# misc.net
KiCad netlist of a schematic drawn in EAGLE
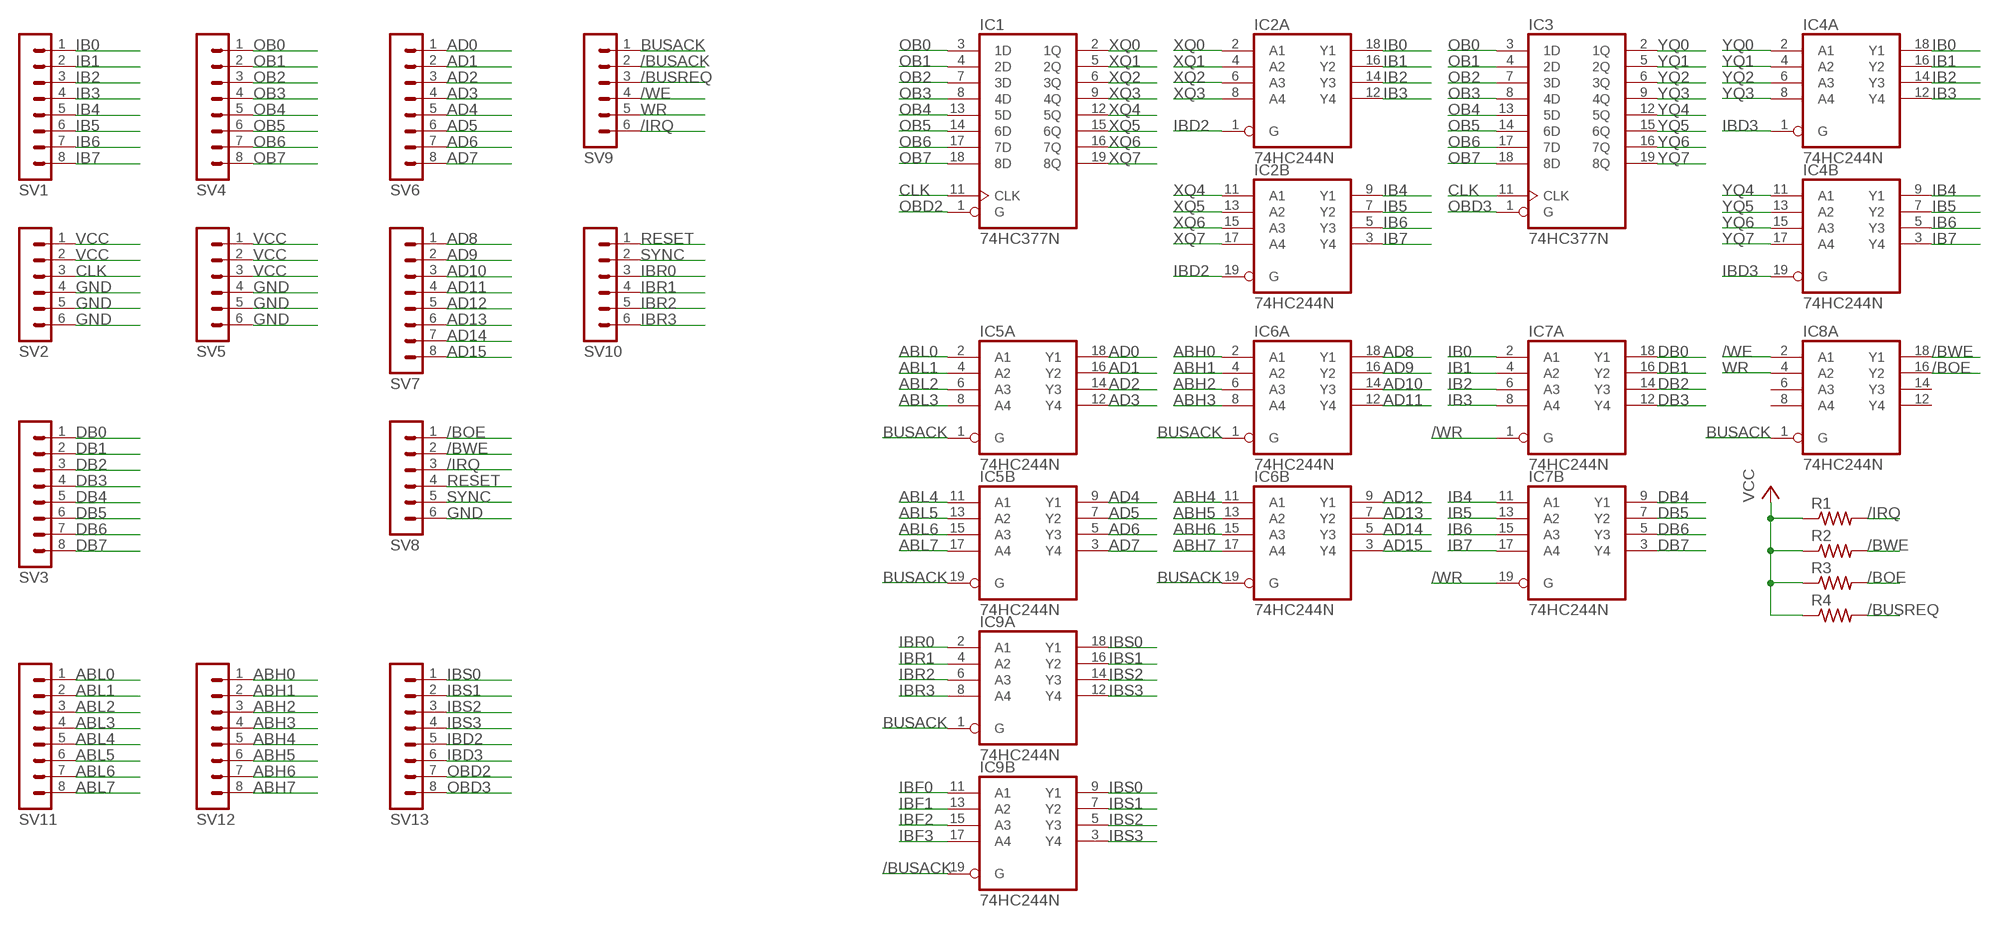
[diagram p0: schematic, sheet 1]

(export (version "E")
  (design (tool "Eeschema 10.0.6"))
  (components
    (comp (ref "IC1")
      (value "74HC377N")
      (footprint "eagle-import:DIL20")
      (libsource (lib "eagle-import") (part "74377NHC"))
    )
    (comp (ref "IC2")
      (value "74HC244N")
      (footprint "eagle-import:DIL20")
      (libsource (lib "eagle-import") (part "74244NHC"))
    )
    (comp (ref "IC3")
      (value "74HC377N")
      (footprint "eagle-import:DIL20")
      (libsource (lib "eagle-import") (part "74377NHC"))
    )
    (comp (ref "IC4")
      (value "74HC244N")
      (footprint "eagle-import:DIL20")
      (libsource (lib "eagle-import") (part "74244NHC"))
    )
    (comp (ref "IC5")
      (value "74HC244N")
      (footprint "eagle-import:DIL20")
      (libsource (lib "eagle-import") (part "74244NHC"))
    )
    (comp (ref "IC6")
      (value "74HC244N")
      (footprint "eagle-import:DIL20")
      (libsource (lib "eagle-import") (part "74244NHC"))
    )
    (comp (ref "IC7")
      (value "74HC244N")
      (footprint "eagle-import:DIL20")
      (libsource (lib "eagle-import") (part "74244NHC"))
    )
    (comp (ref "IC8")
      (value "74HC244N")
      (footprint "eagle-import:DIL20")
      (libsource (lib "eagle-import") (part "74244NHC"))
    )
    (comp (ref "IC9")
      (value "74HC244N")
      (footprint "eagle-import:DIL20")
      (libsource (lib "eagle-import") (part "74244NHC"))
    )
    (comp (ref "R1")
      (value "R-US_0207/10")
      (footprint "eagle-import:0207_10")
      (libsource (lib "eagle-import") (part "R-US_0207/10"))
    )
    (comp (ref "R2")
      (value "R-US_0207/10")
      (footprint "eagle-import:0207_10")
      (libsource (lib "eagle-import") (part "R-US_0207/10"))
    )
    (comp (ref "R3")
      (value "R-US_0207/10")
      (footprint "eagle-import:0207_10")
      (libsource (lib "eagle-import") (part "R-US_0207/10"))
    )
    (comp (ref "R4")
      (value "R-US_0207/10")
      (footprint "eagle-import:0207_10")
      (libsource (lib "eagle-import") (part "R-US_0207/10"))
    )
    (comp (ref "SV1")
      (value "MA08-1")
      (footprint "eagle-import:MA08-1")
      (libsource (lib "eagle-import") (part "MA08-1"))
    )
    (comp (ref "SV2")
      (value "MA06-1")
      (footprint "eagle-import:MA06-1")
      (libsource (lib "eagle-import") (part "MA06-1"))
    )
    (comp (ref "SV3")
      (value "MA08-1")
      (footprint "eagle-import:MA08-1")
      (libsource (lib "eagle-import") (part "MA08-1"))
    )
    (comp (ref "SV4")
      (value "MA08-1")
      (footprint "eagle-import:MA08-1")
      (libsource (lib "eagle-import") (part "MA08-1"))
    )
    (comp (ref "SV5")
      (value "MA06-1")
      (footprint "eagle-import:MA06-1")
      (libsource (lib "eagle-import") (part "MA06-1"))
    )
    (comp (ref "SV6")
      (value "MA08-1")
      (footprint "eagle-import:MA08-1")
      (libsource (lib "eagle-import") (part "MA08-1"))
    )
    (comp (ref "SV7")
      (value "MA08-1")
      (footprint "eagle-import:MA08-1")
      (libsource (lib "eagle-import") (part "MA08-1"))
    )
    (comp (ref "SV8")
      (value "MA06-1")
      (footprint "eagle-import:MA06-1")
      (libsource (lib "eagle-import") (part "MA06-1"))
    )
    (comp (ref "SV9")
      (value "MA06-1")
      (footprint "eagle-import:MA06-1")
      (libsource (lib "eagle-import") (part "MA06-1"))
    )
    (comp (ref "SV10")
      (value "MA06-1")
      (footprint "eagle-import:MA06-1")
      (libsource (lib "eagle-import") (part "MA06-1"))
    )
    (comp (ref "SV11")
      (value "MA08-1")
      (footprint "eagle-import:MA08-1")
      (libsource (lib "eagle-import") (part "MA08-1"))
    )
    (comp (ref "SV12")
      (value "MA08-1")
      (footprint "eagle-import:MA08-1")
      (libsource (lib "eagle-import") (part "MA08-1"))
    )
    (comp (ref "SV13")
      (value "MA08-1")
      (footprint "eagle-import:MA08-1")
      (libsource (lib "eagle-import") (part "MA08-1"))
    )
  )
  (nets
    (net (code "1") (name "/ABH0") (class "Default")
      (node (ref "IC6") (pin "2") (pinfunction "A1_2") (pintype "input"))
      (node (ref "SV12") (pin "1") (pinfunction "1_1") (pintype "passive"))
    )
    (net (code "2") (name "/ABH1") (class "Default")
      (node (ref "IC6") (pin "4") (pinfunction "A2_4") (pintype "input"))
      (node (ref "SV12") (pin "2") (pinfunction "2_2") (pintype "passive"))
    )
    (net (code "3") (name "/ABH2") (class "Default")
      (node (ref "IC6") (pin "6") (pinfunction "A3_6") (pintype "input"))
      (node (ref "SV12") (pin "3") (pinfunction "3_3") (pintype "passive"))
    )
    (net (code "4") (name "/ABH3") (class "Default")
      (node (ref "IC6") (pin "8") (pinfunction "A4_8") (pintype "input"))
      (node (ref "SV12") (pin "4") (pinfunction "4_4") (pintype "passive"))
    )
    (net (code "5") (name "/ABH4") (class "Default")
      (node (ref "IC6") (pin "11") (pinfunction "A1_11") (pintype "input"))
      (node (ref "SV12") (pin "5") (pinfunction "5_5") (pintype "passive"))
    )
    (net (code "6") (name "/ABH5") (class "Default")
      (node (ref "IC6") (pin "13") (pinfunction "A2_13") (pintype "input"))
      (node (ref "SV12") (pin "6") (pinfunction "6_6") (pintype "passive"))
    )
    (net (code "7") (name "/ABH6") (class "Default")
      (node (ref "IC6") (pin "15") (pinfunction "A3_15") (pintype "input"))
      (node (ref "SV12") (pin "7") (pinfunction "7_7") (pintype "passive"))
    )
    (net (code "8") (name "/ABH7") (class "Default")
      (node (ref "IC6") (pin "17") (pinfunction "A4_17") (pintype "input"))
      (node (ref "SV12") (pin "8") (pinfunction "8_8") (pintype "passive"))
    )
    (net (code "9") (name "/ABL0") (class "Default")
      (node (ref "IC5") (pin "2") (pinfunction "A1_2") (pintype "input"))
      (node (ref "SV11") (pin "1") (pinfunction "1_1") (pintype "passive"))
    )
    (net (code "10") (name "/ABL1") (class "Default")
      (node (ref "IC5") (pin "4") (pinfunction "A2_4") (pintype "input"))
      (node (ref "SV11") (pin "2") (pinfunction "2_2") (pintype "passive"))
    )
    (net (code "11") (name "/ABL2") (class "Default")
      (node (ref "IC5") (pin "6") (pinfunction "A3_6") (pintype "input"))
      (node (ref "SV11") (pin "3") (pinfunction "3_3") (pintype "passive"))
    )
    (net (code "12") (name "/ABL3") (class "Default")
      (node (ref "IC5") (pin "8") (pinfunction "A4_8") (pintype "input"))
      (node (ref "SV11") (pin "4") (pinfunction "4_4") (pintype "passive"))
    )
    (net (code "13") (name "/ABL4") (class "Default")
      (node (ref "IC5") (pin "11") (pinfunction "A1_11") (pintype "input"))
      (node (ref "SV11") (pin "5") (pinfunction "5_5") (pintype "passive"))
    )
    (net (code "14") (name "/ABL5") (class "Default")
      (node (ref "IC5") (pin "13") (pinfunction "A2_13") (pintype "input"))
      (node (ref "SV11") (pin "6") (pinfunction "6_6") (pintype "passive"))
    )
    (net (code "15") (name "/ABL6") (class "Default")
      (node (ref "IC5") (pin "15") (pinfunction "A3_15") (pintype "input"))
      (node (ref "SV11") (pin "7") (pinfunction "7_7") (pintype "passive"))
    )
    (net (code "16") (name "/ABL7") (class "Default")
      (node (ref "IC5") (pin "17") (pinfunction "A4_17") (pintype "input"))
      (node (ref "SV11") (pin "8") (pinfunction "8_8") (pintype "passive"))
    )
    (net (code "17") (name "/AD0") (class "Default")
      (node (ref "IC5") (pin "18") (pinfunction "Y1_18") (pintype "tri_state"))
      (node (ref "SV6") (pin "1") (pinfunction "1_1") (pintype "passive"))
    )
    (net (code "18") (name "/AD1") (class "Default")
      (node (ref "IC5") (pin "16") (pinfunction "Y2_16") (pintype "tri_state"))
      (node (ref "SV6") (pin "2") (pinfunction "2_2") (pintype "passive"))
    )
    (net (code "19") (name "/AD2") (class "Default")
      (node (ref "IC5") (pin "14") (pinfunction "Y3_14") (pintype "tri_state"))
      (node (ref "SV6") (pin "3") (pinfunction "3_3") (pintype "passive"))
    )
    (net (code "20") (name "/AD3") (class "Default")
      (node (ref "IC5") (pin "12") (pinfunction "Y4_12") (pintype "tri_state"))
      (node (ref "SV6") (pin "4") (pinfunction "4_4") (pintype "passive"))
    )
    (net (code "21") (name "/AD4") (class "Default")
      (node (ref "IC5") (pin "9") (pinfunction "Y1_9") (pintype "tri_state"))
      (node (ref "SV6") (pin "5") (pinfunction "5_5") (pintype "passive"))
    )
    (net (code "22") (name "/AD5") (class "Default")
      (node (ref "IC5") (pin "7") (pinfunction "Y2_7") (pintype "tri_state"))
      (node (ref "SV6") (pin "6") (pinfunction "6_6") (pintype "passive"))
    )
    (net (code "23") (name "/AD6") (class "Default")
      (node (ref "IC5") (pin "5") (pinfunction "Y3_5") (pintype "tri_state"))
      (node (ref "SV6") (pin "7") (pinfunction "7_7") (pintype "passive"))
    )
    (net (code "24") (name "/AD7") (class "Default")
      (node (ref "IC5") (pin "3") (pinfunction "Y4_3") (pintype "tri_state"))
      (node (ref "SV6") (pin "8") (pinfunction "8_8") (pintype "passive"))
    )
    (net (code "25") (name "/AD8") (class "Default")
      (node (ref "IC6") (pin "18") (pinfunction "Y1_18") (pintype "tri_state"))
      (node (ref "SV7") (pin "1") (pinfunction "1_1") (pintype "passive"))
    )
    (net (code "26") (name "/AD9") (class "Default")
      (node (ref "IC6") (pin "16") (pinfunction "Y2_16") (pintype "tri_state"))
      (node (ref "SV7") (pin "2") (pinfunction "2_2") (pintype "passive"))
    )
    (net (code "27") (name "/AD10") (class "Default")
      (node (ref "IC6") (pin "14") (pinfunction "Y3_14") (pintype "tri_state"))
      (node (ref "SV7") (pin "3") (pinfunction "3_3") (pintype "passive"))
    )
    (net (code "28") (name "/AD11") (class "Default")
      (node (ref "IC6") (pin "12") (pinfunction "Y4_12") (pintype "tri_state"))
      (node (ref "SV7") (pin "4") (pinfunction "4_4") (pintype "passive"))
    )
    (net (code "29") (name "/AD12") (class "Default")
      (node (ref "IC6") (pin "9") (pinfunction "Y1_9") (pintype "tri_state"))
      (node (ref "SV7") (pin "5") (pinfunction "5_5") (pintype "passive"))
    )
    (net (code "30") (name "/AD13") (class "Default")
      (node (ref "IC6") (pin "7") (pinfunction "Y2_7") (pintype "tri_state"))
      (node (ref "SV7") (pin "6") (pinfunction "6_6") (pintype "passive"))
    )
    (net (code "31") (name "/AD14") (class "Default")
      (node (ref "IC6") (pin "5") (pinfunction "Y3_5") (pintype "tri_state"))
      (node (ref "SV7") (pin "7") (pinfunction "7_7") (pintype "passive"))
    )
    (net (code "32") (name "/AD15") (class "Default")
      (node (ref "IC6") (pin "3") (pinfunction "Y4_3") (pintype "tri_state"))
      (node (ref "SV7") (pin "8") (pinfunction "8_8") (pintype "passive"))
    )
    (net (code "33") (name "/BUSACK") (class "Default")
      (node (ref "IC5") (pin "1") (pinfunction "G_1") (pintype "input"))
      (node (ref "IC5") (pin "19") (pinfunction "G_19") (pintype "input"))
      (node (ref "IC6") (pin "1") (pinfunction "G_1") (pintype "input"))
      (node (ref "IC6") (pin "19") (pinfunction "G_19") (pintype "input"))
      (node (ref "IC8") (pin "1") (pinfunction "G_1") (pintype "input"))
      (node (ref "IC9") (pin "1") (pinfunction "G_1") (pintype "input"))
      (node (ref "SV9") (pin "1") (pinfunction "1_1") (pintype "passive"))
    )
    (net (code "34") (name "/CLK") (class "Default")
      (node (ref "IC1") (pin "11") (pinfunction "CLK_11") (pintype "input"))
      (node (ref "IC3") (pin "11") (pinfunction "CLK_11") (pintype "input"))
      (node (ref "SV2") (pin "3") (pinfunction "3_3") (pintype "passive"))
    )
    (net (code "35") (name "/DB0") (class "Default")
      (node (ref "IC7") (pin "18") (pinfunction "Y1_18") (pintype "tri_state"))
      (node (ref "SV3") (pin "1") (pinfunction "1_1") (pintype "passive"))
    )
    (net (code "36") (name "/DB1") (class "Default")
      (node (ref "IC7") (pin "16") (pinfunction "Y2_16") (pintype "tri_state"))
      (node (ref "SV3") (pin "2") (pinfunction "2_2") (pintype "passive"))
    )
    (net (code "37") (name "/DB2") (class "Default")
      (node (ref "IC7") (pin "14") (pinfunction "Y3_14") (pintype "tri_state"))
      (node (ref "SV3") (pin "3") (pinfunction "3_3") (pintype "passive"))
    )
    (net (code "38") (name "/DB3") (class "Default")
      (node (ref "IC7") (pin "12") (pinfunction "Y4_12") (pintype "tri_state"))
      (node (ref "SV3") (pin "4") (pinfunction "4_4") (pintype "passive"))
    )
    (net (code "39") (name "/DB4") (class "Default")
      (node (ref "IC7") (pin "9") (pinfunction "Y1_9") (pintype "tri_state"))
      (node (ref "SV3") (pin "5") (pinfunction "5_5") (pintype "passive"))
    )
    (net (code "40") (name "/DB5") (class "Default")
      (node (ref "IC7") (pin "7") (pinfunction "Y2_7") (pintype "tri_state"))
      (node (ref "SV3") (pin "6") (pinfunction "6_6") (pintype "passive"))
    )
    (net (code "41") (name "/DB6") (class "Default")
      (node (ref "IC7") (pin "5") (pinfunction "Y3_5") (pintype "tri_state"))
      (node (ref "SV3") (pin "7") (pinfunction "7_7") (pintype "passive"))
    )
    (net (code "42") (name "/DB7") (class "Default")
      (node (ref "IC7") (pin "3") (pinfunction "Y4_3") (pintype "tri_state"))
      (node (ref "SV3") (pin "8") (pinfunction "8_8") (pintype "passive"))
    )
    (net (code "43") (name "/GND") (class "Default")
      (node (ref "SV2") (pin "4") (pinfunction "4_4") (pintype "passive"))
      (node (ref "SV2") (pin "5") (pinfunction "5_5") (pintype "passive"))
      (node (ref "SV2") (pin "6") (pinfunction "6_6") (pintype "passive"))
      (node (ref "SV5") (pin "4") (pinfunction "4_4") (pintype "passive"))
      (node (ref "SV5") (pin "5") (pinfunction "5_5") (pintype "passive"))
      (node (ref "SV5") (pin "6") (pinfunction "6_6") (pintype "passive"))
      (node (ref "SV8") (pin "6") (pinfunction "6_6") (pintype "passive"))
    )
    (net (code "44") (name "/IB0") (class "Default")
      (node (ref "IC2") (pin "18") (pinfunction "Y1_18") (pintype "tri_state"))
      (node (ref "IC4") (pin "18") (pinfunction "Y1_18") (pintype "tri_state"))
      (node (ref "IC7") (pin "2") (pinfunction "A1_2") (pintype "input"))
      (node (ref "SV1") (pin "1") (pinfunction "1_1") (pintype "passive"))
    )
    (net (code "45") (name "/IB1") (class "Default")
      (node (ref "IC2") (pin "16") (pinfunction "Y2_16") (pintype "tri_state"))
      (node (ref "IC4") (pin "16") (pinfunction "Y2_16") (pintype "tri_state"))
      (node (ref "IC7") (pin "4") (pinfunction "A2_4") (pintype "input"))
      (node (ref "SV1") (pin "2") (pinfunction "2_2") (pintype "passive"))
    )
    (net (code "46") (name "/IB2") (class "Default")
      (node (ref "IC2") (pin "14") (pinfunction "Y3_14") (pintype "tri_state"))
      (node (ref "IC4") (pin "14") (pinfunction "Y3_14") (pintype "tri_state"))
      (node (ref "IC7") (pin "6") (pinfunction "A3_6") (pintype "input"))
      (node (ref "SV1") (pin "3") (pinfunction "3_3") (pintype "passive"))
    )
    (net (code "47") (name "/IB3") (class "Default")
      (node (ref "IC2") (pin "12") (pinfunction "Y4_12") (pintype "tri_state"))
      (node (ref "IC4") (pin "12") (pinfunction "Y4_12") (pintype "tri_state"))
      (node (ref "IC7") (pin "8") (pinfunction "A4_8") (pintype "input"))
      (node (ref "SV1") (pin "4") (pinfunction "4_4") (pintype "passive"))
    )
    (net (code "48") (name "/IB4") (class "Default")
      (node (ref "IC2") (pin "9") (pinfunction "Y1_9") (pintype "tri_state"))
      (node (ref "IC4") (pin "9") (pinfunction "Y1_9") (pintype "tri_state"))
      (node (ref "IC7") (pin "11") (pinfunction "A1_11") (pintype "input"))
      (node (ref "SV1") (pin "5") (pinfunction "5_5") (pintype "passive"))
    )
    (net (code "49") (name "/IB5") (class "Default")
      (node (ref "IC2") (pin "7") (pinfunction "Y2_7") (pintype "tri_state"))
      (node (ref "IC4") (pin "7") (pinfunction "Y2_7") (pintype "tri_state"))
      (node (ref "IC7") (pin "13") (pinfunction "A2_13") (pintype "input"))
      (node (ref "SV1") (pin "6") (pinfunction "6_6") (pintype "passive"))
    )
    (net (code "50") (name "/IB6") (class "Default")
      (node (ref "IC2") (pin "5") (pinfunction "Y3_5") (pintype "tri_state"))
      (node (ref "IC4") (pin "5") (pinfunction "Y3_5") (pintype "tri_state"))
      (node (ref "IC7") (pin "15") (pinfunction "A3_15") (pintype "input"))
      (node (ref "SV1") (pin "7") (pinfunction "7_7") (pintype "passive"))
    )
    (net (code "51") (name "/IB7") (class "Default")
      (node (ref "IC2") (pin "3") (pinfunction "Y4_3") (pintype "tri_state"))
      (node (ref "IC4") (pin "3") (pinfunction "Y4_3") (pintype "tri_state"))
      (node (ref "IC7") (pin "17") (pinfunction "A4_17") (pintype "input"))
      (node (ref "SV1") (pin "8") (pinfunction "8_8") (pintype "passive"))
    )
    (net (code "52") (name "/IBD2") (class "Default")
      (node (ref "IC2") (pin "1") (pinfunction "G_1") (pintype "input"))
      (node (ref "IC2") (pin "19") (pinfunction "G_19") (pintype "input"))
      (node (ref "SV13") (pin "5") (pinfunction "5_5") (pintype "passive"))
    )
    (net (code "53") (name "/IBD3") (class "Default")
      (node (ref "IC4") (pin "1") (pinfunction "G_1") (pintype "input"))
      (node (ref "IC4") (pin "19") (pinfunction "G_19") (pintype "input"))
      (node (ref "SV13") (pin "6") (pinfunction "6_6") (pintype "passive"))
    )
    (net (code "54") (name "/IBF0") (class "Default")
      (node (ref "IC9") (pin "11") (pinfunction "A1_11") (pintype "input"))
    )
    (net (code "55") (name "/IBF1") (class "Default")
      (node (ref "IC9") (pin "13") (pinfunction "A2_13") (pintype "input"))
    )
    (net (code "56") (name "/IBF2") (class "Default")
      (node (ref "IC9") (pin "15") (pinfunction "A3_15") (pintype "input"))
    )
    (net (code "57") (name "/IBF3") (class "Default")
      (node (ref "IC9") (pin "17") (pinfunction "A4_17") (pintype "input"))
    )
    (net (code "58") (name "/IBR0") (class "Default")
      (node (ref "IC9") (pin "2") (pinfunction "A1_2") (pintype "input"))
      (node (ref "SV10") (pin "3") (pinfunction "3_3") (pintype "passive"))
    )
    (net (code "59") (name "/IBR1") (class "Default")
      (node (ref "IC9") (pin "4") (pinfunction "A2_4") (pintype "input"))
      (node (ref "SV10") (pin "4") (pinfunction "4_4") (pintype "passive"))
    )
    (net (code "60") (name "/IBR2") (class "Default")
      (node (ref "IC9") (pin "6") (pinfunction "A3_6") (pintype "input"))
      (node (ref "SV10") (pin "5") (pinfunction "5_5") (pintype "passive"))
    )
    (net (code "61") (name "/IBR3") (class "Default")
      (node (ref "IC9") (pin "8") (pinfunction "A4_8") (pintype "input"))
      (node (ref "SV10") (pin "6") (pinfunction "6_6") (pintype "passive"))
    )
    (net (code "62") (name "/IBS0") (class "Default")
      (node (ref "IC9") (pin "18") (pinfunction "Y1_18") (pintype "tri_state"))
      (node (ref "IC9") (pin "9") (pinfunction "Y1_9") (pintype "tri_state"))
      (node (ref "SV13") (pin "1") (pinfunction "1_1") (pintype "passive"))
    )
    (net (code "63") (name "/IBS1") (class "Default")
      (node (ref "IC9") (pin "16") (pinfunction "Y2_16") (pintype "tri_state"))
      (node (ref "IC9") (pin "7") (pinfunction "Y2_7") (pintype "tri_state"))
      (node (ref "SV13") (pin "2") (pinfunction "2_2") (pintype "passive"))
    )
    (net (code "64") (name "/IBS2") (class "Default")
      (node (ref "IC9") (pin "14") (pinfunction "Y3_14") (pintype "tri_state"))
      (node (ref "IC9") (pin "5") (pinfunction "Y3_5") (pintype "tri_state"))
      (node (ref "SV13") (pin "3") (pinfunction "3_3") (pintype "passive"))
    )
    (net (code "65") (name "/IBS3") (class "Default")
      (node (ref "IC9") (pin "12") (pinfunction "Y4_12") (pintype "tri_state"))
      (node (ref "IC9") (pin "3") (pinfunction "Y4_3") (pintype "tri_state"))
      (node (ref "SV13") (pin "4") (pinfunction "4_4") (pintype "passive"))
    )
    (net (code "66") (name "/OB0") (class "Default")
      (node (ref "IC1") (pin "3") (pinfunction "1D_3") (pintype "input"))
      (node (ref "IC3") (pin "3") (pinfunction "1D_3") (pintype "input"))
      (node (ref "SV4") (pin "1") (pinfunction "1_1") (pintype "passive"))
    )
    (net (code "67") (name "/OB1") (class "Default")
      (node (ref "IC1") (pin "4") (pinfunction "2D_4") (pintype "input"))
      (node (ref "IC3") (pin "4") (pinfunction "2D_4") (pintype "input"))
      (node (ref "SV4") (pin "2") (pinfunction "2_2") (pintype "passive"))
    )
    (net (code "68") (name "/OB2") (class "Default")
      (node (ref "IC1") (pin "7") (pinfunction "3D_7") (pintype "input"))
      (node (ref "IC3") (pin "7") (pinfunction "3D_7") (pintype "input"))
      (node (ref "SV4") (pin "3") (pinfunction "3_3") (pintype "passive"))
    )
    (net (code "69") (name "/OB3") (class "Default")
      (node (ref "IC1") (pin "8") (pinfunction "4D_8") (pintype "input"))
      (node (ref "IC3") (pin "8") (pinfunction "4D_8") (pintype "input"))
      (node (ref "SV4") (pin "4") (pinfunction "4_4") (pintype "passive"))
    )
    (net (code "70") (name "/OB4") (class "Default")
      (node (ref "IC1") (pin "13") (pinfunction "5D_13") (pintype "input"))
      (node (ref "IC3") (pin "13") (pinfunction "5D_13") (pintype "input"))
      (node (ref "SV4") (pin "5") (pinfunction "5_5") (pintype "passive"))
    )
    (net (code "71") (name "/OB5") (class "Default")
      (node (ref "IC1") (pin "14") (pinfunction "6D_14") (pintype "input"))
      (node (ref "IC3") (pin "14") (pinfunction "6D_14") (pintype "input"))
      (node (ref "SV4") (pin "6") (pinfunction "6_6") (pintype "passive"))
    )
    (net (code "72") (name "/OB6") (class "Default")
      (node (ref "IC1") (pin "17") (pinfunction "7D_17") (pintype "input"))
      (node (ref "IC3") (pin "17") (pinfunction "7D_17") (pintype "input"))
      (node (ref "SV4") (pin "7") (pinfunction "7_7") (pintype "passive"))
    )
    (net (code "73") (name "/OB7") (class "Default")
      (node (ref "IC1") (pin "18") (pinfunction "8D_18") (pintype "input"))
      (node (ref "IC3") (pin "18") (pinfunction "8D_18") (pintype "input"))
      (node (ref "SV4") (pin "8") (pinfunction "8_8") (pintype "passive"))
    )
    (net (code "74") (name "/OBD2") (class "Default")
      (node (ref "IC1") (pin "1") (pinfunction "G_1") (pintype "input"))
      (node (ref "SV13") (pin "7") (pinfunction "7_7") (pintype "passive"))
    )
    (net (code "75") (name "/OBD3") (class "Default")
      (node (ref "IC3") (pin "1") (pinfunction "G_1") (pintype "input"))
      (node (ref "SV13") (pin "8") (pinfunction "8_8") (pintype "passive"))
    )
    (net (code "76") (name "/RESET") (class "Default")
      (node (ref "SV10") (pin "1") (pinfunction "1_1") (pintype "passive"))
      (node (ref "SV8") (pin "4") (pinfunction "4_4") (pintype "passive"))
    )
    (net (code "77") (name "/SYNC") (class "Default")
      (node (ref "SV10") (pin "2") (pinfunction "2_2") (pintype "passive"))
      (node (ref "SV8") (pin "5") (pinfunction "5_5") (pintype "passive"))
    )
    (net (code "78") (name "/WR") (class "Default")
      (node (ref "IC8") (pin "4") (pinfunction "A2_4") (pintype "input"))
      (node (ref "SV9") (pin "5") (pinfunction "5_5") (pintype "passive"))
    )
    (net (code "79") (name "/XQ0") (class "Default")
      (node (ref "IC1") (pin "2") (pinfunction "1Q_2") (pintype "output"))
      (node (ref "IC2") (pin "2") (pinfunction "A1_2") (pintype "input"))
    )
    (net (code "80") (name "/XQ1") (class "Default")
      (node (ref "IC1") (pin "5") (pinfunction "2Q_5") (pintype "output"))
      (node (ref "IC2") (pin "4") (pinfunction "A2_4") (pintype "input"))
    )
    (net (code "81") (name "/XQ2") (class "Default")
      (node (ref "IC1") (pin "6") (pinfunction "3Q_6") (pintype "output"))
      (node (ref "IC2") (pin "6") (pinfunction "A3_6") (pintype "input"))
    )
    (net (code "82") (name "/XQ3") (class "Default")
      (node (ref "IC1") (pin "9") (pinfunction "4Q_9") (pintype "output"))
      (node (ref "IC2") (pin "8") (pinfunction "A4_8") (pintype "input"))
    )
    (net (code "83") (name "/XQ4") (class "Default")
      (node (ref "IC1") (pin "12") (pinfunction "5Q_12") (pintype "output"))
      (node (ref "IC2") (pin "11") (pinfunction "A1_11") (pintype "input"))
    )
    (net (code "84") (name "/XQ5") (class "Default")
      (node (ref "IC1") (pin "15") (pinfunction "6Q_15") (pintype "output"))
      (node (ref "IC2") (pin "13") (pinfunction "A2_13") (pintype "input"))
    )
    (net (code "85") (name "/XQ6") (class "Default")
      (node (ref "IC1") (pin "16") (pinfunction "7Q_16") (pintype "output"))
      (node (ref "IC2") (pin "15") (pinfunction "A3_15") (pintype "input"))
    )
    (net (code "86") (name "/XQ7") (class "Default")
      (node (ref "IC1") (pin "19") (pinfunction "8Q_19") (pintype "output"))
      (node (ref "IC2") (pin "17") (pinfunction "A4_17") (pintype "input"))
    )
    (net (code "87") (name "/YQ0") (class "Default")
      (node (ref "IC3") (pin "2") (pinfunction "1Q_2") (pintype "output"))
      (node (ref "IC4") (pin "2") (pinfunction "A1_2") (pintype "input"))
    )
    (net (code "88") (name "/YQ1") (class "Default")
      (node (ref "IC3") (pin "5") (pinfunction "2Q_5") (pintype "output"))
      (node (ref "IC4") (pin "4") (pinfunction "A2_4") (pintype "input"))
    )
    (net (code "89") (name "/YQ2") (class "Default")
      (node (ref "IC3") (pin "6") (pinfunction "3Q_6") (pintype "output"))
      (node (ref "IC4") (pin "6") (pinfunction "A3_6") (pintype "input"))
    )
    (net (code "90") (name "/YQ3") (class "Default")
      (node (ref "IC3") (pin "9") (pinfunction "4Q_9") (pintype "output"))
      (node (ref "IC4") (pin "8") (pinfunction "A4_8") (pintype "input"))
    )
    (net (code "91") (name "/YQ4") (class "Default")
      (node (ref "IC3") (pin "12") (pinfunction "5Q_12") (pintype "output"))
      (node (ref "IC4") (pin "11") (pinfunction "A1_11") (pintype "input"))
    )
    (net (code "92") (name "/YQ5") (class "Default")
      (node (ref "IC3") (pin "15") (pinfunction "6Q_15") (pintype "output"))
      (node (ref "IC4") (pin "13") (pinfunction "A2_13") (pintype "input"))
    )
    (net (code "93") (name "/YQ6") (class "Default")
      (node (ref "IC3") (pin "16") (pinfunction "7Q_16") (pintype "output"))
      (node (ref "IC4") (pin "15") (pinfunction "A3_15") (pintype "input"))
    )
    (net (code "94") (name "/YQ7") (class "Default")
      (node (ref "IC3") (pin "19") (pinfunction "8Q_19") (pintype "output"))
      (node (ref "IC4") (pin "17") (pinfunction "A4_17") (pintype "input"))
    )
    (net (code "95") (name "/{slash}BOE") (class "Default")
      (node (ref "IC8") (pin "16") (pinfunction "Y2_16") (pintype "tri_state"))
      (node (ref "R3") (pin "2") (pinfunction "2_2") (pintype "passive"))
      (node (ref "SV8") (pin "1") (pinfunction "1_1") (pintype "passive"))
    )
    (net (code "96") (name "/{slash}BUSACK") (class "Default")
      (node (ref "IC9") (pin "19") (pinfunction "G_19") (pintype "input"))
      (node (ref "SV9") (pin "2") (pinfunction "2_2") (pintype "passive"))
    )
    (net (code "97") (name "/{slash}BUSREQ") (class "Default")
      (node (ref "R4") (pin "2") (pinfunction "2_2") (pintype "passive"))
      (node (ref "SV9") (pin "3") (pinfunction "3_3") (pintype "passive"))
    )
    (net (code "98") (name "/{slash}BWE") (class "Default")
      (node (ref "IC8") (pin "18") (pinfunction "Y1_18") (pintype "tri_state"))
      (node (ref "R2") (pin "2") (pinfunction "2_2") (pintype "passive"))
      (node (ref "SV8") (pin "2") (pinfunction "2_2") (pintype "passive"))
    )
    (net (code "99") (name "/{slash}IRQ") (class "Default")
      (node (ref "R1") (pin "2") (pinfunction "2_2") (pintype "passive"))
      (node (ref "SV8") (pin "3") (pinfunction "3_3") (pintype "passive"))
      (node (ref "SV9") (pin "6") (pinfunction "6_6") (pintype "passive"))
    )
    (net (code "100") (name "/{slash}WE") (class "Default")
      (node (ref "IC8") (pin "2") (pinfunction "A1_2") (pintype "input"))
      (node (ref "SV9") (pin "4") (pinfunction "4_4") (pintype "passive"))
    )
    (net (code "101") (name "/{slash}WR") (class "Default")
      (node (ref "IC7") (pin "1") (pinfunction "G_1") (pintype "input"))
      (node (ref "IC7") (pin "19") (pinfunction "G_19") (pintype "input"))
    )
    (net (code "102") (name "VCC") (class "Default")
      (node (ref "R1") (pin "1") (pinfunction "1_1") (pintype "passive"))
      (node (ref "R2") (pin "1") (pinfunction "1_1") (pintype "passive"))
      (node (ref "R3") (pin "1") (pinfunction "1_1") (pintype "passive"))
      (node (ref "R4") (pin "1") (pinfunction "1_1") (pintype "passive"))
      (node (ref "SV2") (pin "1") (pinfunction "1_1") (pintype "passive"))
      (node (ref "SV2") (pin "2") (pinfunction "2_2") (pintype "passive"))
      (node (ref "SV5") (pin "1") (pinfunction "1_1") (pintype "passive"))
      (node (ref "SV5") (pin "2") (pinfunction "2_2") (pintype "passive"))
      (node (ref "SV5") (pin "3") (pinfunction "3_3") (pintype "passive"))
    )
    (net (code "103") (name "unconnected-(IC8A-A3-Pad6)") (class "Default")
      (node (ref "IC8") (pin "6") (pinfunction "A3_6") (pintype "input"))
    )
    (net (code "104") (name "unconnected-(IC8A-A4-Pad8)") (class "Default")
      (node (ref "IC8") (pin "8") (pinfunction "A4_8") (pintype "input"))
    )
    (net (code "105") (name "unconnected-(IC8A-Y3-Pad14)") (class "Default")
      (node (ref "IC8") (pin "14") (pinfunction "Y3_14") (pintype "tri_state"))
    )
    (net (code "106") (name "unconnected-(IC8A-Y4-Pad12)") (class "Default")
      (node (ref "IC8") (pin "12") (pinfunction "Y4_12") (pintype "tri_state"))
    )
  )
)
